# kirchhoff.net
KiCad netlist of a schematic drawn in EAGLE
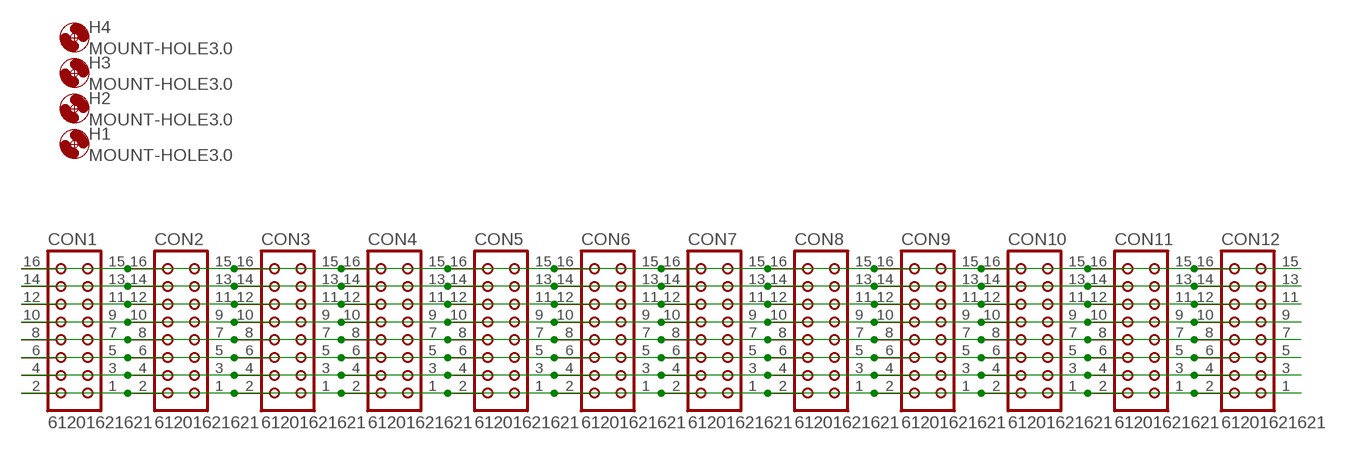
[diagram p0: schematic, sheet 1]

(export (version "E")
  (design (tool "Eeschema 10.0.6"))
  (components
    (comp (ref "CON1")
      (value "61201621621")
      (footprint "eagle-import:CON16L")
      (libsource (lib "eagle-import") (part "CON16L"))
    )
    (comp (ref "CON2")
      (value "61201621621")
      (footprint "eagle-import:CON16L")
      (libsource (lib "eagle-import") (part "CON16L"))
    )
    (comp (ref "CON3")
      (value "61201621621")
      (footprint "eagle-import:CON16L")
      (libsource (lib "eagle-import") (part "CON16L"))
    )
    (comp (ref "CON4")
      (value "61201621621")
      (footprint "eagle-import:CON16L")
      (libsource (lib "eagle-import") (part "CON16L"))
    )
    (comp (ref "CON5")
      (value "61201621621")
      (footprint "eagle-import:CON16L")
      (libsource (lib "eagle-import") (part "CON16L"))
    )
    (comp (ref "CON6")
      (value "61201621621")
      (footprint "eagle-import:CON16L")
      (libsource (lib "eagle-import") (part "CON16L"))
    )
    (comp (ref "CON7")
      (value "61201621621")
      (footprint "eagle-import:CON16L")
      (libsource (lib "eagle-import") (part "CON16L"))
    )
    (comp (ref "CON8")
      (value "61201621621")
      (footprint "eagle-import:CON16L")
      (libsource (lib "eagle-import") (part "CON16L"))
    )
    (comp (ref "CON9")
      (value "61201621621")
      (footprint "eagle-import:CON16L")
      (libsource (lib "eagle-import") (part "CON16L"))
    )
    (comp (ref "CON10")
      (value "61201621621")
      (footprint "eagle-import:CON16L")
      (libsource (lib "eagle-import") (part "CON16L"))
    )
    (comp (ref "CON11")
      (value "61201621621")
      (footprint "eagle-import:CON16L")
      (libsource (lib "eagle-import") (part "CON16L"))
    )
    (comp (ref "CON12")
      (value "61201621621")
      (footprint "eagle-import:CON16L")
      (libsource (lib "eagle-import") (part "CON16L"))
    )
    (comp (ref "H1")
      (value "MOUNT-HOLE3.0")
      (footprint "eagle-import:3,0")
      (libsource (lib "eagle-import") (part "MOUNT-HOLE3.0"))
    )
    (comp (ref "H2")
      (value "MOUNT-HOLE3.0")
      (footprint "eagle-import:3,0")
      (libsource (lib "eagle-import") (part "MOUNT-HOLE3.0"))
    )
    (comp (ref "H3")
      (value "MOUNT-HOLE3.0")
      (footprint "eagle-import:3,0")
      (libsource (lib "eagle-import") (part "MOUNT-HOLE3.0"))
    )
    (comp (ref "H4")
      (value "MOUNT-HOLE3.0")
      (footprint "eagle-import:3,0")
      (libsource (lib "eagle-import") (part "MOUNT-HOLE3.0"))
    )
  )
  (nets
    (net (code "1") (name "Net-(CON1-Pad1)") (class "Default")
      (node (ref "CON1") (pin "1") (pinfunction "1_1") (pintype "passive"))
      (node (ref "CON1") (pin "2") (pinfunction "2_2") (pintype "passive"))
      (node (ref "CON10") (pin "1") (pinfunction "1_1") (pintype "passive"))
      (node (ref "CON10") (pin "2") (pinfunction "2_2") (pintype "passive"))
      (node (ref "CON11") (pin "1") (pinfunction "1_1") (pintype "passive"))
      (node (ref "CON11") (pin "2") (pinfunction "2_2") (pintype "passive"))
      (node (ref "CON12") (pin "1") (pinfunction "1_1") (pintype "passive"))
      (node (ref "CON12") (pin "2") (pinfunction "2_2") (pintype "passive"))
      (node (ref "CON2") (pin "1") (pinfunction "1_1") (pintype "passive"))
      (node (ref "CON2") (pin "2") (pinfunction "2_2") (pintype "passive"))
      (node (ref "CON3") (pin "1") (pinfunction "1_1") (pintype "passive"))
      (node (ref "CON3") (pin "2") (pinfunction "2_2") (pintype "passive"))
      (node (ref "CON4") (pin "1") (pinfunction "1_1") (pintype "passive"))
      (node (ref "CON4") (pin "2") (pinfunction "2_2") (pintype "passive"))
      (node (ref "CON5") (pin "1") (pinfunction "1_1") (pintype "passive"))
      (node (ref "CON5") (pin "2") (pinfunction "2_2") (pintype "passive"))
      (node (ref "CON6") (pin "1") (pinfunction "1_1") (pintype "passive"))
      (node (ref "CON6") (pin "2") (pinfunction "2_2") (pintype "passive"))
      (node (ref "CON7") (pin "1") (pinfunction "1_1") (pintype "passive"))
      (node (ref "CON7") (pin "2") (pinfunction "2_2") (pintype "passive"))
      (node (ref "CON8") (pin "1") (pinfunction "1_1") (pintype "passive"))
      (node (ref "CON8") (pin "2") (pinfunction "2_2") (pintype "passive"))
      (node (ref "CON9") (pin "1") (pinfunction "1_1") (pintype "passive"))
      (node (ref "CON9") (pin "2") (pinfunction "2_2") (pintype "passive"))
    )
    (net (code "2") (name "Net-(CON1-Pad3)") (class "Default")
      (node (ref "CON1") (pin "3") (pinfunction "3_3") (pintype "passive"))
      (node (ref "CON1") (pin "4") (pinfunction "4_4") (pintype "passive"))
      (node (ref "CON10") (pin "3") (pinfunction "3_3") (pintype "passive"))
      (node (ref "CON10") (pin "4") (pinfunction "4_4") (pintype "passive"))
      (node (ref "CON11") (pin "3") (pinfunction "3_3") (pintype "passive"))
      (node (ref "CON11") (pin "4") (pinfunction "4_4") (pintype "passive"))
      (node (ref "CON12") (pin "3") (pinfunction "3_3") (pintype "passive"))
      (node (ref "CON12") (pin "4") (pinfunction "4_4") (pintype "passive"))
      (node (ref "CON2") (pin "3") (pinfunction "3_3") (pintype "passive"))
      (node (ref "CON2") (pin "4") (pinfunction "4_4") (pintype "passive"))
      (node (ref "CON3") (pin "3") (pinfunction "3_3") (pintype "passive"))
      (node (ref "CON3") (pin "4") (pinfunction "4_4") (pintype "passive"))
      (node (ref "CON4") (pin "3") (pinfunction "3_3") (pintype "passive"))
      (node (ref "CON4") (pin "4") (pinfunction "4_4") (pintype "passive"))
      (node (ref "CON5") (pin "3") (pinfunction "3_3") (pintype "passive"))
      (node (ref "CON5") (pin "4") (pinfunction "4_4") (pintype "passive"))
      (node (ref "CON6") (pin "3") (pinfunction "3_3") (pintype "passive"))
      (node (ref "CON6") (pin "4") (pinfunction "4_4") (pintype "passive"))
      (node (ref "CON7") (pin "3") (pinfunction "3_3") (pintype "passive"))
      (node (ref "CON7") (pin "4") (pinfunction "4_4") (pintype "passive"))
      (node (ref "CON8") (pin "3") (pinfunction "3_3") (pintype "passive"))
      (node (ref "CON8") (pin "4") (pinfunction "4_4") (pintype "passive"))
      (node (ref "CON9") (pin "3") (pinfunction "3_3") (pintype "passive"))
      (node (ref "CON9") (pin "4") (pinfunction "4_4") (pintype "passive"))
    )
    (net (code "3") (name "Net-(CON1-Pad5)") (class "Default")
      (node (ref "CON1") (pin "5") (pinfunction "5_5") (pintype "passive"))
      (node (ref "CON1") (pin "6") (pinfunction "6_6") (pintype "passive"))
      (node (ref "CON10") (pin "5") (pinfunction "5_5") (pintype "passive"))
      (node (ref "CON10") (pin "6") (pinfunction "6_6") (pintype "passive"))
      (node (ref "CON11") (pin "5") (pinfunction "5_5") (pintype "passive"))
      (node (ref "CON11") (pin "6") (pinfunction "6_6") (pintype "passive"))
      (node (ref "CON12") (pin "5") (pinfunction "5_5") (pintype "passive"))
      (node (ref "CON12") (pin "6") (pinfunction "6_6") (pintype "passive"))
      (node (ref "CON2") (pin "5") (pinfunction "5_5") (pintype "passive"))
      (node (ref "CON2") (pin "6") (pinfunction "6_6") (pintype "passive"))
      (node (ref "CON3") (pin "5") (pinfunction "5_5") (pintype "passive"))
      (node (ref "CON3") (pin "6") (pinfunction "6_6") (pintype "passive"))
      (node (ref "CON4") (pin "5") (pinfunction "5_5") (pintype "passive"))
      (node (ref "CON4") (pin "6") (pinfunction "6_6") (pintype "passive"))
      (node (ref "CON5") (pin "5") (pinfunction "5_5") (pintype "passive"))
      (node (ref "CON5") (pin "6") (pinfunction "6_6") (pintype "passive"))
      (node (ref "CON6") (pin "5") (pinfunction "5_5") (pintype "passive"))
      (node (ref "CON6") (pin "6") (pinfunction "6_6") (pintype "passive"))
      (node (ref "CON7") (pin "5") (pinfunction "5_5") (pintype "passive"))
      (node (ref "CON7") (pin "6") (pinfunction "6_6") (pintype "passive"))
      (node (ref "CON8") (pin "5") (pinfunction "5_5") (pintype "passive"))
      (node (ref "CON8") (pin "6") (pinfunction "6_6") (pintype "passive"))
      (node (ref "CON9") (pin "5") (pinfunction "5_5") (pintype "passive"))
      (node (ref "CON9") (pin "6") (pinfunction "6_6") (pintype "passive"))
    )
    (net (code "4") (name "Net-(CON1-Pad7)") (class "Default")
      (node (ref "CON1") (pin "7") (pinfunction "7_7") (pintype "passive"))
      (node (ref "CON1") (pin "8") (pinfunction "8_8") (pintype "passive"))
      (node (ref "CON10") (pin "7") (pinfunction "7_7") (pintype "passive"))
      (node (ref "CON10") (pin "8") (pinfunction "8_8") (pintype "passive"))
      (node (ref "CON11") (pin "7") (pinfunction "7_7") (pintype "passive"))
      (node (ref "CON11") (pin "8") (pinfunction "8_8") (pintype "passive"))
      (node (ref "CON12") (pin "7") (pinfunction "7_7") (pintype "passive"))
      (node (ref "CON12") (pin "8") (pinfunction "8_8") (pintype "passive"))
      (node (ref "CON2") (pin "7") (pinfunction "7_7") (pintype "passive"))
      (node (ref "CON2") (pin "8") (pinfunction "8_8") (pintype "passive"))
      (node (ref "CON3") (pin "7") (pinfunction "7_7") (pintype "passive"))
      (node (ref "CON3") (pin "8") (pinfunction "8_8") (pintype "passive"))
      (node (ref "CON4") (pin "7") (pinfunction "7_7") (pintype "passive"))
      (node (ref "CON4") (pin "8") (pinfunction "8_8") (pintype "passive"))
      (node (ref "CON5") (pin "7") (pinfunction "7_7") (pintype "passive"))
      (node (ref "CON5") (pin "8") (pinfunction "8_8") (pintype "passive"))
      (node (ref "CON6") (pin "7") (pinfunction "7_7") (pintype "passive"))
      (node (ref "CON6") (pin "8") (pinfunction "8_8") (pintype "passive"))
      (node (ref "CON7") (pin "7") (pinfunction "7_7") (pintype "passive"))
      (node (ref "CON7") (pin "8") (pinfunction "8_8") (pintype "passive"))
      (node (ref "CON8") (pin "7") (pinfunction "7_7") (pintype "passive"))
      (node (ref "CON8") (pin "8") (pinfunction "8_8") (pintype "passive"))
      (node (ref "CON9") (pin "7") (pinfunction "7_7") (pintype "passive"))
      (node (ref "CON9") (pin "8") (pinfunction "8_8") (pintype "passive"))
    )
    (net (code "5") (name "Net-(CON1-Pad10)") (class "Default")
      (node (ref "CON1") (pin "10") (pinfunction "10_10") (pintype "passive"))
      (node (ref "CON1") (pin "9") (pinfunction "9_9") (pintype "passive"))
      (node (ref "CON10") (pin "10") (pinfunction "10_10") (pintype "passive"))
      (node (ref "CON10") (pin "9") (pinfunction "9_9") (pintype "passive"))
      (node (ref "CON11") (pin "10") (pinfunction "10_10") (pintype "passive"))
      (node (ref "CON11") (pin "9") (pinfunction "9_9") (pintype "passive"))
      (node (ref "CON12") (pin "10") (pinfunction "10_10") (pintype "passive"))
      (node (ref "CON12") (pin "9") (pinfunction "9_9") (pintype "passive"))
      (node (ref "CON2") (pin "10") (pinfunction "10_10") (pintype "passive"))
      (node (ref "CON2") (pin "9") (pinfunction "9_9") (pintype "passive"))
      (node (ref "CON3") (pin "10") (pinfunction "10_10") (pintype "passive"))
      (node (ref "CON3") (pin "9") (pinfunction "9_9") (pintype "passive"))
      (node (ref "CON4") (pin "10") (pinfunction "10_10") (pintype "passive"))
      (node (ref "CON4") (pin "9") (pinfunction "9_9") (pintype "passive"))
      (node (ref "CON5") (pin "10") (pinfunction "10_10") (pintype "passive"))
      (node (ref "CON5") (pin "9") (pinfunction "9_9") (pintype "passive"))
      (node (ref "CON6") (pin "10") (pinfunction "10_10") (pintype "passive"))
      (node (ref "CON6") (pin "9") (pinfunction "9_9") (pintype "passive"))
      (node (ref "CON7") (pin "10") (pinfunction "10_10") (pintype "passive"))
      (node (ref "CON7") (pin "9") (pinfunction "9_9") (pintype "passive"))
      (node (ref "CON8") (pin "10") (pinfunction "10_10") (pintype "passive"))
      (node (ref "CON8") (pin "9") (pinfunction "9_9") (pintype "passive"))
      (node (ref "CON9") (pin "10") (pinfunction "10_10") (pintype "passive"))
      (node (ref "CON9") (pin "9") (pinfunction "9_9") (pintype "passive"))
    )
    (net (code "6") (name "Net-(CON1-Pad11)") (class "Default")
      (node (ref "CON1") (pin "11") (pinfunction "11_11") (pintype "passive"))
      (node (ref "CON1") (pin "12") (pinfunction "12_12") (pintype "passive"))
      (node (ref "CON10") (pin "11") (pinfunction "11_11") (pintype "passive"))
      (node (ref "CON10") (pin "12") (pinfunction "12_12") (pintype "passive"))
      (node (ref "CON11") (pin "11") (pinfunction "11_11") (pintype "passive"))
      (node (ref "CON11") (pin "12") (pinfunction "12_12") (pintype "passive"))
      (node (ref "CON12") (pin "11") (pinfunction "11_11") (pintype "passive"))
      (node (ref "CON12") (pin "12") (pinfunction "12_12") (pintype "passive"))
      (node (ref "CON2") (pin "11") (pinfunction "11_11") (pintype "passive"))
      (node (ref "CON2") (pin "12") (pinfunction "12_12") (pintype "passive"))
      (node (ref "CON3") (pin "11") (pinfunction "11_11") (pintype "passive"))
      (node (ref "CON3") (pin "12") (pinfunction "12_12") (pintype "passive"))
      (node (ref "CON4") (pin "11") (pinfunction "11_11") (pintype "passive"))
      (node (ref "CON4") (pin "12") (pinfunction "12_12") (pintype "passive"))
      (node (ref "CON5") (pin "11") (pinfunction "11_11") (pintype "passive"))
      (node (ref "CON5") (pin "12") (pinfunction "12_12") (pintype "passive"))
      (node (ref "CON6") (pin "11") (pinfunction "11_11") (pintype "passive"))
      (node (ref "CON6") (pin "12") (pinfunction "12_12") (pintype "passive"))
      (node (ref "CON7") (pin "11") (pinfunction "11_11") (pintype "passive"))
      (node (ref "CON7") (pin "12") (pinfunction "12_12") (pintype "passive"))
      (node (ref "CON8") (pin "11") (pinfunction "11_11") (pintype "passive"))
      (node (ref "CON8") (pin "12") (pinfunction "12_12") (pintype "passive"))
      (node (ref "CON9") (pin "11") (pinfunction "11_11") (pintype "passive"))
      (node (ref "CON9") (pin "12") (pinfunction "12_12") (pintype "passive"))
    )
    (net (code "7") (name "Net-(CON1-Pad13)") (class "Default")
      (node (ref "CON1") (pin "13") (pinfunction "13_13") (pintype "passive"))
      (node (ref "CON1") (pin "14") (pinfunction "14_14") (pintype "passive"))
      (node (ref "CON10") (pin "13") (pinfunction "13_13") (pintype "passive"))
      (node (ref "CON10") (pin "14") (pinfunction "14_14") (pintype "passive"))
      (node (ref "CON11") (pin "13") (pinfunction "13_13") (pintype "passive"))
      (node (ref "CON11") (pin "14") (pinfunction "14_14") (pintype "passive"))
      (node (ref "CON12") (pin "13") (pinfunction "13_13") (pintype "passive"))
      (node (ref "CON12") (pin "14") (pinfunction "14_14") (pintype "passive"))
      (node (ref "CON2") (pin "13") (pinfunction "13_13") (pintype "passive"))
      (node (ref "CON2") (pin "14") (pinfunction "14_14") (pintype "passive"))
      (node (ref "CON3") (pin "13") (pinfunction "13_13") (pintype "passive"))
      (node (ref "CON3") (pin "14") (pinfunction "14_14") (pintype "passive"))
      (node (ref "CON4") (pin "13") (pinfunction "13_13") (pintype "passive"))
      (node (ref "CON4") (pin "14") (pinfunction "14_14") (pintype "passive"))
      (node (ref "CON5") (pin "13") (pinfunction "13_13") (pintype "passive"))
      (node (ref "CON5") (pin "14") (pinfunction "14_14") (pintype "passive"))
      (node (ref "CON6") (pin "13") (pinfunction "13_13") (pintype "passive"))
      (node (ref "CON6") (pin "14") (pinfunction "14_14") (pintype "passive"))
      (node (ref "CON7") (pin "13") (pinfunction "13_13") (pintype "passive"))
      (node (ref "CON7") (pin "14") (pinfunction "14_14") (pintype "passive"))
      (node (ref "CON8") (pin "13") (pinfunction "13_13") (pintype "passive"))
      (node (ref "CON8") (pin "14") (pinfunction "14_14") (pintype "passive"))
      (node (ref "CON9") (pin "13") (pinfunction "13_13") (pintype "passive"))
      (node (ref "CON9") (pin "14") (pinfunction "14_14") (pintype "passive"))
    )
    (net (code "8") (name "Net-(CON1-Pad15)") (class "Default")
      (node (ref "CON1") (pin "15") (pinfunction "15_15") (pintype "passive"))
      (node (ref "CON1") (pin "16") (pinfunction "16_16") (pintype "passive"))
      (node (ref "CON10") (pin "15") (pinfunction "15_15") (pintype "passive"))
      (node (ref "CON10") (pin "16") (pinfunction "16_16") (pintype "passive"))
      (node (ref "CON11") (pin "15") (pinfunction "15_15") (pintype "passive"))
      (node (ref "CON11") (pin "16") (pinfunction "16_16") (pintype "passive"))
      (node (ref "CON12") (pin "15") (pinfunction "15_15") (pintype "passive"))
      (node (ref "CON12") (pin "16") (pinfunction "16_16") (pintype "passive"))
      (node (ref "CON2") (pin "15") (pinfunction "15_15") (pintype "passive"))
      (node (ref "CON2") (pin "16") (pinfunction "16_16") (pintype "passive"))
      (node (ref "CON3") (pin "15") (pinfunction "15_15") (pintype "passive"))
      (node (ref "CON3") (pin "16") (pinfunction "16_16") (pintype "passive"))
      (node (ref "CON4") (pin "15") (pinfunction "15_15") (pintype "passive"))
      (node (ref "CON4") (pin "16") (pinfunction "16_16") (pintype "passive"))
      (node (ref "CON5") (pin "15") (pinfunction "15_15") (pintype "passive"))
      (node (ref "CON5") (pin "16") (pinfunction "16_16") (pintype "passive"))
      (node (ref "CON6") (pin "15") (pinfunction "15_15") (pintype "passive"))
      (node (ref "CON6") (pin "16") (pinfunction "16_16") (pintype "passive"))
      (node (ref "CON7") (pin "15") (pinfunction "15_15") (pintype "passive"))
      (node (ref "CON7") (pin "16") (pinfunction "16_16") (pintype "passive"))
      (node (ref "CON8") (pin "15") (pinfunction "15_15") (pintype "passive"))
      (node (ref "CON8") (pin "16") (pinfunction "16_16") (pintype "passive"))
      (node (ref "CON9") (pin "15") (pinfunction "15_15") (pintype "passive"))
      (node (ref "CON9") (pin "16") (pinfunction "16_16") (pintype "passive"))
    )
  )
)
